# conn.net
KiCad netlist of a schematic drawn in Altium Designer
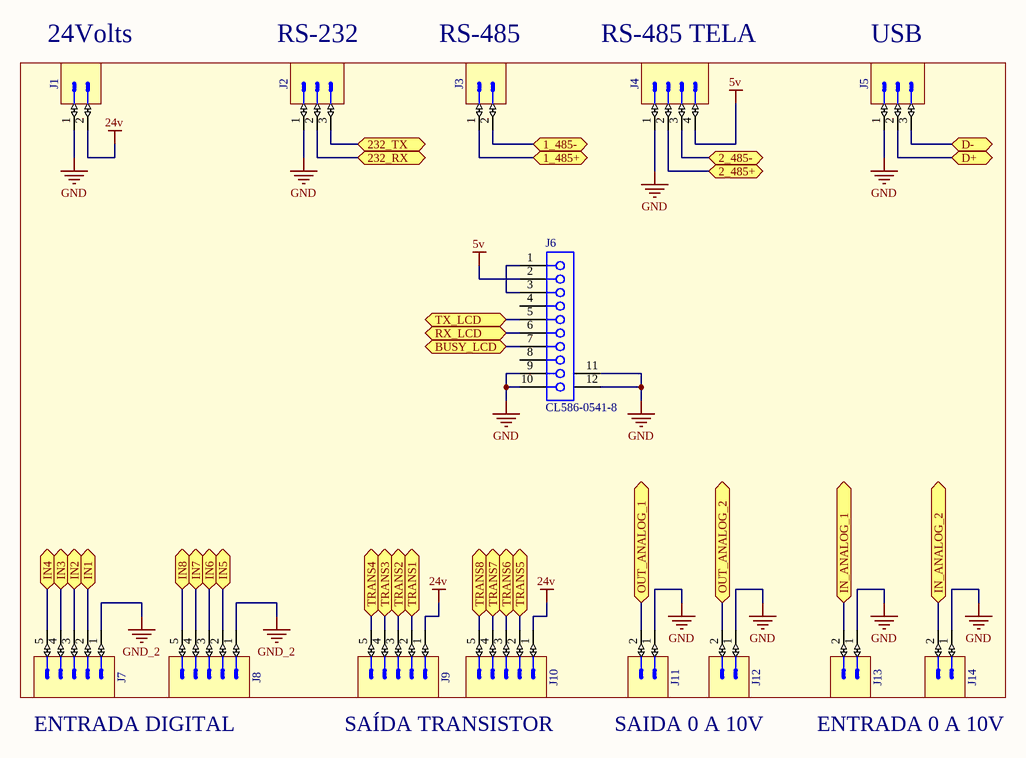
[diagram p0: conn.SchDoc]

(export (version "E")
  (design (tool "Eeschema 10.0.6"))
  (components
    (comp (ref "J1")
      (value "~")
      (footprint "PHOENIX_1757242")
      (description "Connector 2 Male")
      (fields
        (field (name "PART NUMBER") "PHOENIX_1757242")
        (field (name "MANUFACTURER") "PHOENIX CONTACT")
        (field (name "AUTHOR") "CERN DEM JLC")
      )
      (libsource (lib "") (part "Connector 2 Male_1"))
    )
    (comp (ref "J2")
      (value "~")
      (footprint "PHOENIX_1757255")
      (description "Connector 3 Male")
      (fields
        (field (name "PART NUMBER") "PHOENIX_1757255")
        (field (name "MANUFACTURER") "PHOENIX CONTACT")
        (field (name "AUTHOR") "CERN DEM JLC")
      )
      (libsource (lib "Connectors") (part "Connector 3 Male"))
    )
    (comp (ref "J3")
      (value "~")
      (footprint "PHOENIX_1757242")
      (description "Connector 2 Male")
      (fields
        (field (name "PART NUMBER") "PHOENIX_1757242")
        (field (name "MANUFACTURER") "PHOENIX CONTACT")
        (field (name "AUTHOR") "CERN DEM JLC")
      )
      (libsource (lib "") (part "Connector 2 Male_1"))
    )
    (comp (ref "J4")
      (value "~")
      (footprint "PHOENIX_1757268")
      (description "Connector 4 Male")
      (fields
        (field (name "PART NUMBER") "PHOENIX_1757268")
        (field (name "MANUFACTURER") "PHOENIX CONTACT")
        (field (name "AUTHOR") "CERN DEM JLC")
      )
      (libsource (lib "Connectors") (part "Connector 4 Male"))
    )
    (comp (ref "J5")
      (value "~")
      (footprint "PHOENIX_1757255")
      (description "Connector 3 Male")
      (fields
        (field (name "PART NUMBER") "PHOENIX_1757255")
        (field (name "MANUFACTURER") "PHOENIX CONTACT")
        (field (name "AUTHOR") "CERN DEM JLC")
      )
      (libsource (lib "Connectors") (part "Connector 3 Male"))
    )
    (comp (ref "J6")
      (value "CL586-0541-8")
      (footprint "FH12-22(10)SA-1SH")
      (description "FH12 Series, \"Flip-Lock\" SMT/ZIF FFC/FPC Connector - 1.0mm Spaced Bottom Eccentric Contact")
      (fields (field (name "PUBLISHER") "Altium Limited"))
      (libsource (lib "HRS FPC-FFC FH12 Series") (part "CL586-0541-8"))
    )
    (comp (ref "J7")
      (value "~")
      (footprint "PHOENIX_1803303")
      (description "Connector 5 Male")
      (fields
        (field (name "PART NUMBER") "PHOENIX_1803303")
        (field (name "MANUFACTURER") "PHOENIX CONTACT")
        (field (name "AUTHOR") "CERN DEM JLC")
      )
      (libsource (lib "Connectors") (part "Connector 5 Male"))
    )
    (comp (ref "J8")
      (value "~")
      (footprint "PHOENIX_1803303")
      (description "Connector 5 Male")
      (fields
        (field (name "PART NUMBER") "PHOENIX_1803303")
        (field (name "MANUFACTURER") "PHOENIX CONTACT")
        (field (name "AUTHOR") "CERN DEM JLC")
      )
      (libsource (lib "Connectors") (part "Connector 5 Male"))
    )
    (comp (ref "J9")
      (value "~")
      (footprint "PHOENIX_1803303")
      (description "Connector 5 Male")
      (fields
        (field (name "PART NUMBER") "PHOENIX_1803303")
        (field (name "MANUFACTURER") "PHOENIX CONTACT")
        (field (name "AUTHOR") "CERN DEM JLC")
      )
      (libsource (lib "Connectors") (part "Connector 5 Male"))
    )
    (comp (ref "J10")
      (value "~")
      (footprint "PHOENIX_1803303")
      (description "Connector 5 Male")
      (fields
        (field (name "PART NUMBER") "PHOENIX_1803303")
        (field (name "MANUFACTURER") "PHOENIX CONTACT")
        (field (name "AUTHOR") "CERN DEM JLC")
      )
      (libsource (lib "Connectors") (part "Connector 5 Male"))
    )
    (comp (ref "J11")
      (value "~")
      (footprint "PHOENIX_1757242")
      (description "Connector 2 Male")
      (fields
        (field (name "PART NUMBER") "PHOENIX_1757242")
        (field (name "MANUFACTURER") "PHOENIX CONTACT")
        (field (name "AUTHOR") "CERN DEM JLC")
      )
      (libsource (lib "Connectors") (part "Connector 2 Male"))
    )
    (comp (ref "J12")
      (value "~")
      (footprint "PHOENIX_1757242")
      (description "Connector 2 Male")
      (fields
        (field (name "PART NUMBER") "PHOENIX_1757242")
        (field (name "MANUFACTURER") "PHOENIX CONTACT")
        (field (name "AUTHOR") "CERN DEM JLC")
      )
      (libsource (lib "Connectors") (part "Connector 2 Male"))
    )
    (comp (ref "J13")
      (value "~")
      (footprint "PHOENIX_1757242")
      (description "Connector 2 Male")
      (fields
        (field (name "PART NUMBER") "PHOENIX_1757242")
        (field (name "MANUFACTURER") "PHOENIX CONTACT")
        (field (name "AUTHOR") "CERN DEM JLC")
      )
      (libsource (lib "Connectors") (part "Connector 2 Male"))
    )
    (comp (ref "J14")
      (value "~")
      (footprint "PHOENIX_1757242")
      (description "Connector 2 Male")
      (fields
        (field (name "PART NUMBER") "PHOENIX_1757242")
        (field (name "MANUFACTURER") "PHOENIX CONTACT")
        (field (name "AUTHOR") "CERN DEM JLC")
      )
      (libsource (lib "Connectors") (part "Connector 2 Male"))
    )
  )
  (nets
    (net (code "1") (name "/1_485+") (class "Default")
      (node (ref "J3") (pin "1") (pinfunction "1_1") (pintype "bidirectional"))
    )
    (net (code "2") (name "/1_485-") (class "Default")
      (node (ref "J3") (pin "2") (pinfunction "2_2") (pintype "bidirectional"))
    )
    (net (code "3") (name "/2_485+") (class "Default")
      (node (ref "J4") (pin "2") (pinfunction "2_2") (pintype "bidirectional"))
    )
    (net (code "4") (name "/2_485-") (class "Default")
      (node (ref "J4") (pin "3") (pinfunction "3_3") (pintype "bidirectional"))
    )
    (net (code "5") (name "/232_RX") (class "Default")
      (node (ref "J2") (pin "2") (pinfunction "2_2") (pintype "bidirectional"))
    )
    (net (code "6") (name "/232_TX") (class "Default")
      (node (ref "J2") (pin "3") (pinfunction "3_3") (pintype "bidirectional"))
    )
    (net (code "7") (name "/BUSY_LCD") (class "Default")
      (node (ref "J6") (pin "7") (pinfunction "7_7") (pintype "passive"))
    )
    (net (code "8") (name "/D+") (class "Default")
      (node (ref "J5") (pin "2") (pinfunction "2_2") (pintype "bidirectional"))
    )
    (net (code "9") (name "/D-") (class "Default")
      (node (ref "J5") (pin "3") (pinfunction "3_3") (pintype "bidirectional"))
    )
    (net (code "10") (name "/IN1") (class "Default")
      (node (ref "J7") (pin "2") (pinfunction "2_2") (pintype "bidirectional"))
    )
    (net (code "11") (name "/IN2") (class "Default")
      (node (ref "J7") (pin "3") (pinfunction "3_3") (pintype "bidirectional"))
    )
    (net (code "12") (name "/IN3") (class "Default")
      (node (ref "J7") (pin "4") (pinfunction "4_4") (pintype "bidirectional"))
    )
    (net (code "13") (name "/IN4") (class "Default")
      (node (ref "J7") (pin "5") (pinfunction "5_5") (pintype "bidirectional"))
    )
    (net (code "14") (name "/IN5") (class "Default")
      (node (ref "J8") (pin "2") (pinfunction "2_2") (pintype "bidirectional"))
    )
    (net (code "15") (name "/IN6") (class "Default")
      (node (ref "J8") (pin "3") (pinfunction "3_3") (pintype "bidirectional"))
    )
    (net (code "16") (name "/IN7") (class "Default")
      (node (ref "J8") (pin "4") (pinfunction "4_4") (pintype "bidirectional"))
    )
    (net (code "17") (name "/IN8") (class "Default")
      (node (ref "J8") (pin "5") (pinfunction "5_5") (pintype "bidirectional"))
    )
    (net (code "18") (name "/IN_ANALOG_1") (class "Default")
      (node (ref "J13") (pin "2") (pinfunction "2_2") (pintype "bidirectional"))
    )
    (net (code "19") (name "/IN_ANALOG_2") (class "Default")
      (node (ref "J14") (pin "2") (pinfunction "2_2") (pintype "bidirectional"))
    )
    (net (code "20") (name "/OUT_ANALOG_1") (class "Default")
      (node (ref "J11") (pin "2") (pinfunction "2_2") (pintype "bidirectional"))
    )
    (net (code "21") (name "/OUT_ANALOG_2") (class "Default")
      (node (ref "J12") (pin "2") (pinfunction "2_2") (pintype "bidirectional"))
    )
    (net (code "22") (name "/RX_LCD") (class "Default")
      (node (ref "J6") (pin "6") (pinfunction "6_6") (pintype "passive"))
    )
    (net (code "23") (name "/TRANS1") (class "Default")
      (node (ref "J9") (pin "2") (pinfunction "2_2") (pintype "bidirectional"))
    )
    (net (code "24") (name "/TRANS2") (class "Default")
      (node (ref "J9") (pin "3") (pinfunction "3_3") (pintype "bidirectional"))
    )
    (net (code "25") (name "/TRANS3") (class "Default")
      (node (ref "J9") (pin "4") (pinfunction "4_4") (pintype "bidirectional"))
    )
    (net (code "26") (name "/TRANS4") (class "Default")
      (node (ref "J9") (pin "5") (pinfunction "5_5") (pintype "bidirectional"))
    )
    (net (code "27") (name "/TRANS5") (class "Default")
      (node (ref "J10") (pin "2") (pinfunction "2_2") (pintype "bidirectional"))
    )
    (net (code "28") (name "/TRANS6") (class "Default")
      (node (ref "J10") (pin "3") (pinfunction "3_3") (pintype "bidirectional"))
    )
    (net (code "29") (name "/TRANS7") (class "Default")
      (node (ref "J10") (pin "4") (pinfunction "4_4") (pintype "bidirectional"))
    )
    (net (code "30") (name "/TRANS8") (class "Default")
      (node (ref "J10") (pin "5") (pinfunction "5_5") (pintype "bidirectional"))
    )
    (net (code "31") (name "/TX_LCD") (class "Default")
      (node (ref "J6") (pin "5") (pinfunction "5_5") (pintype "passive"))
    )
    (net (code "32") (name "5v") (class "Default")
      (node (ref "J4") (pin "4") (pinfunction "4_4") (pintype "bidirectional"))
      (node (ref "J6") (pin "2") (pinfunction "2_2") (pintype "passive"))
    )
    (net (code "33") (name "24v") (class "Default")
      (node (ref "J1") (pin "2") (pinfunction "2_2") (pintype "bidirectional"))
      (node (ref "J10") (pin "1") (pinfunction "1_1") (pintype "bidirectional"))
      (node (ref "J9") (pin "1") (pinfunction "1_1") (pintype "bidirectional"))
    )
    (net (code "34") (name "GND") (class "Default")
      (node (ref "J1") (pin "1") (pinfunction "1_1") (pintype "bidirectional"))
      (node (ref "J11") (pin "1") (pinfunction "1_1") (pintype "bidirectional"))
      (node (ref "J12") (pin "1") (pinfunction "1_1") (pintype "bidirectional"))
      (node (ref "J13") (pin "1") (pinfunction "1_1") (pintype "bidirectional"))
      (node (ref "J14") (pin "1") (pinfunction "1_1") (pintype "bidirectional"))
      (node (ref "J2") (pin "1") (pinfunction "1_1") (pintype "bidirectional"))
      (node (ref "J4") (pin "1") (pinfunction "1_1") (pintype "bidirectional"))
      (node (ref "J5") (pin "1") (pinfunction "1_1") (pintype "bidirectional"))
      (node (ref "J6") (pin "10") (pinfunction "10_10") (pintype "passive"))
      (node (ref "J6") (pin "11") (pinfunction "MH1_11") (pintype "passive"))
      (node (ref "J6") (pin "12") (pinfunction "MH2_12") (pintype "passive"))
      (node (ref "J6") (pin "9") (pinfunction "9_9") (pintype "passive"))
    )
    (net (code "35") (name "GND_2") (class "Default")
      (node (ref "J7") (pin "1") (pinfunction "1_1") (pintype "bidirectional"))
      (node (ref "J8") (pin "1") (pinfunction "1_1") (pintype "bidirectional"))
    )
    (net (code "36") (name "Net-(J6-Pad1)") (class "Default")
      (node (ref "J6") (pin "1") (pinfunction "1_1") (pintype "passive"))
      (node (ref "J6") (pin "3") (pinfunction "3_3") (pintype "passive"))
    )
    (net (code "37") (name "unconnected-(J6-Pad4)") (class "Default")
      (node (ref "J6") (pin "4") (pinfunction "4_4") (pintype "passive"))
    )
    (net (code "38") (name "unconnected-(J6-Pad8)") (class "Default")
      (node (ref "J6") (pin "8") (pinfunction "8_8") (pintype "passive"))
    )
  )
)
